# Sheet_1_2022-10-20.net
KiCad netlist of a schematic drawn in Altium Designer
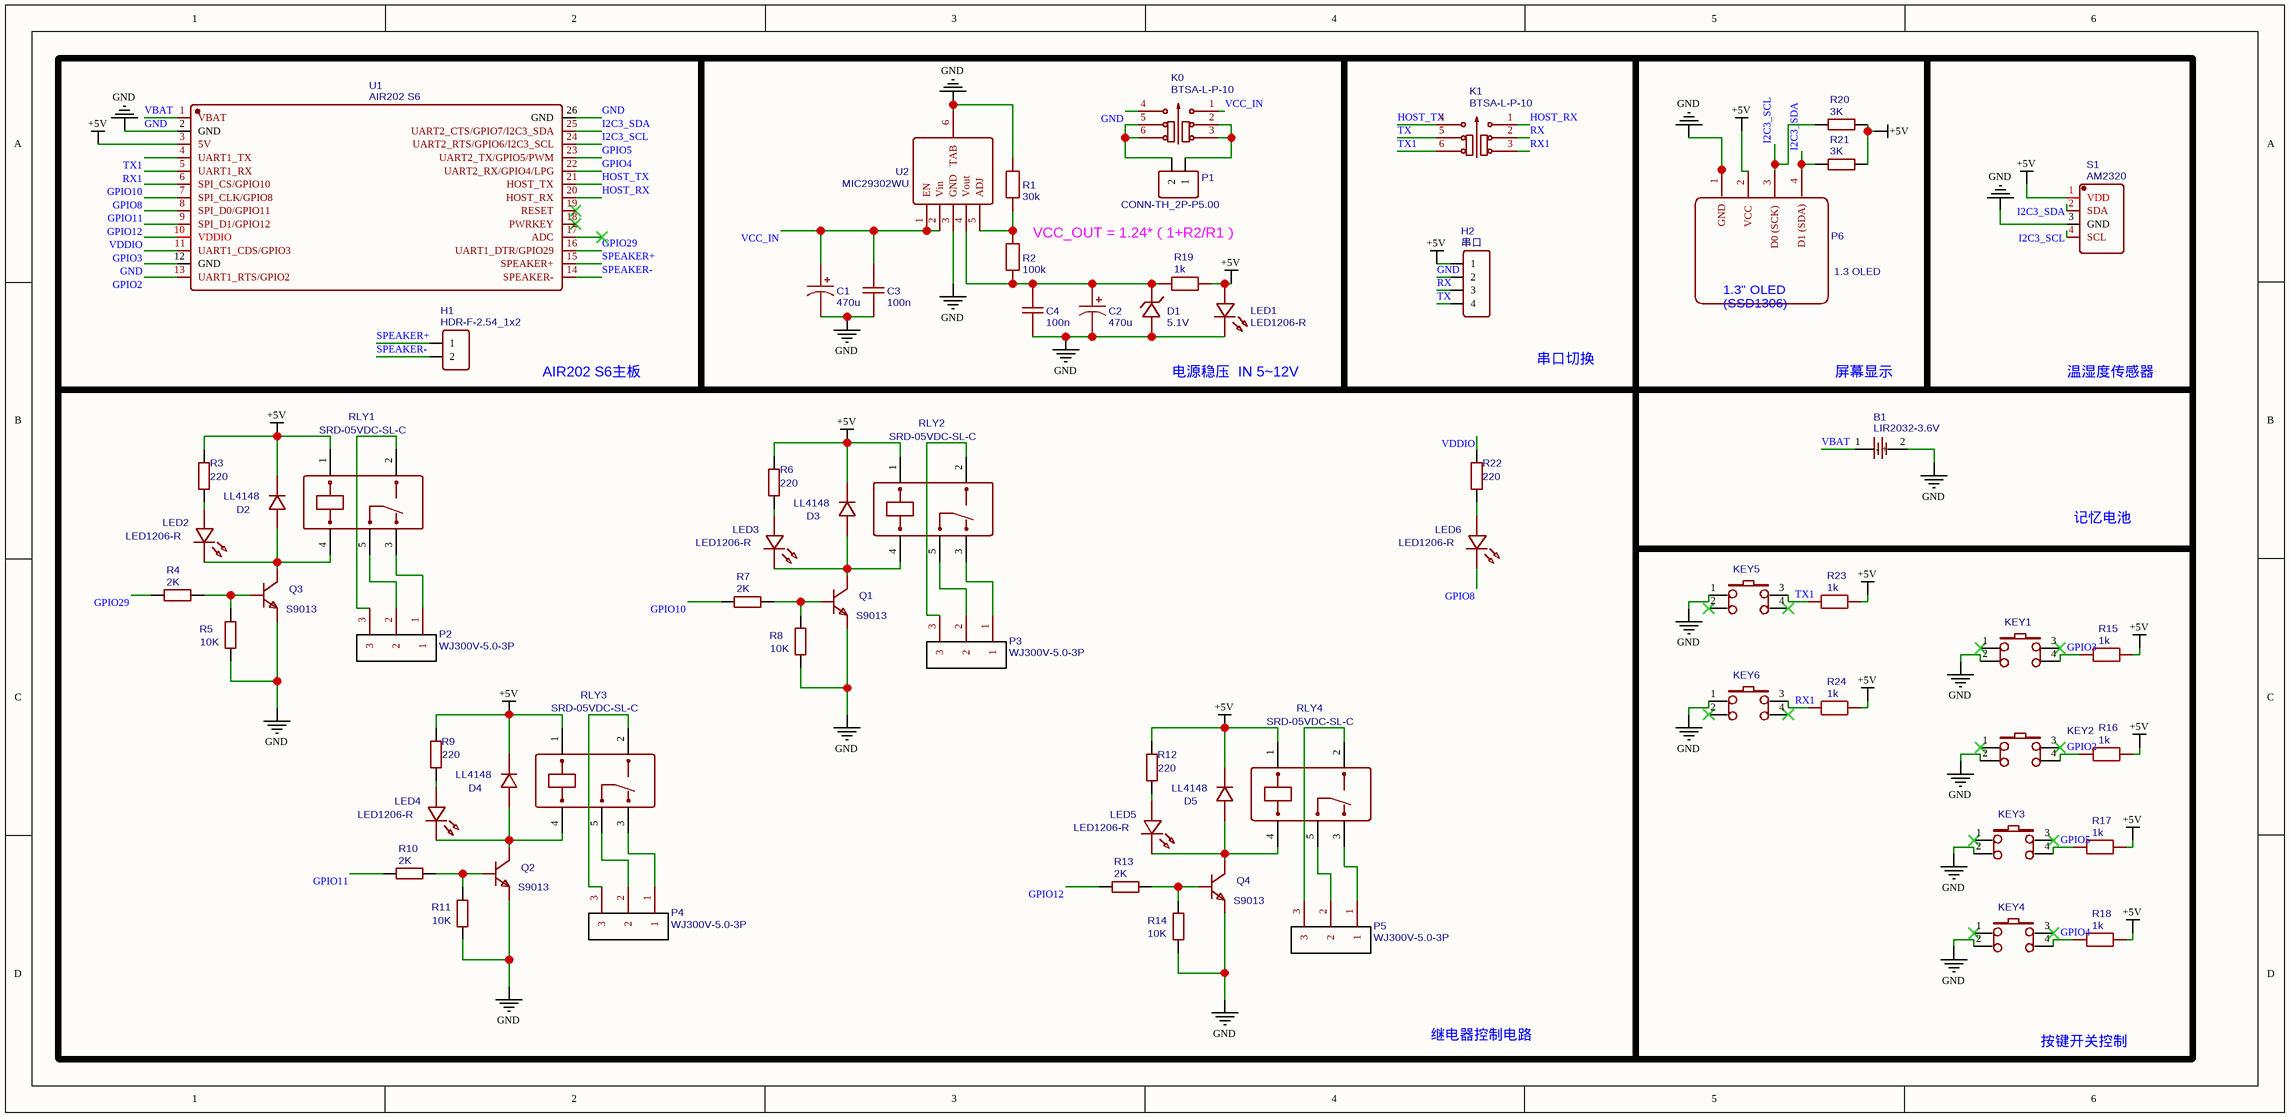
[diagram p0: Sheet_1_2022-10-20.schdoc]

(export (version "E")
  (design (tool "Eeschema 10.0.6"))
  (components
    (comp (ref "B1")
      (value "LIR2032-3.6V")
      (fields
        (field (name "BOM_MANUFACTURER PART") "CR2032-BS-6-1")
        (field (name "BOM_SUPPLIER PART") "C70377")
        (field (name "CONTRIBUTOR") "壹科团队")
      )
      (libsource (lib "altium-import") (part "root_0_LIR2032-3.6V_"))
    )
    (comp (ref "C1")
      (value "470u")
      (fields (field (name "CONTRIBUTOR") "LCEDA_Lib"))
      (libsource (lib "altium-import") (part "root_3_470u_"))
    )
    (comp (ref "C2")
      (value "470u")
      (fields (field (name "CONTRIBUTOR") "LCEDA_Lib"))
      (libsource (lib "altium-import") (part "root_3_470u_"))
    )
    (comp (ref "C3")
      (value "100n")
      (fields (field (name "CONTRIBUTOR") "LCEDA_Lib"))
      (libsource (lib "altium-import") (part "root_3_100n_"))
    )
    (comp (ref "C4")
      (value "100n")
      (fields (field (name "CONTRIBUTOR") "LCEDA_Lib"))
      (libsource (lib "altium-import") (part "root_3_100n_"))
    )
    (comp (ref "D1")
      (value "5.1V")
      (fields
        (field (name "BOM_MANUFACTURER PART") "BZD27B75P-M3-08")
        (field (name "BOM_SUPPLIER PART") "C145219")
        (field (name "CONTRIBUTOR") "LCSC")
      )
      (libsource (lib "altium-import") (part "root_3_5.1V_"))
    )
    (comp (ref "D2")
      (value "LL4148")
      (fields (field (name "BOM_SUPPLIER PART") "C84062"))
      (libsource (lib "altium-import") (part "root_3_LL4148_"))
    )
    (comp (ref "D3")
      (value "LL4148")
      (fields (field (name "BOM_SUPPLIER PART") "C84062"))
      (libsource (lib "altium-import") (part "root_3_LL4148_"))
    )
    (comp (ref "D4")
      (value "LL4148")
      (fields (field (name "BOM_SUPPLIER PART") "C84062"))
      (libsource (lib "altium-import") (part "root_3_LL4148_"))
    )
    (comp (ref "D5")
      (value "LL4148")
      (fields (field (name "BOM_SUPPLIER PART") "C84062"))
      (libsource (lib "altium-import") (part "root_3_LL4148_"))
    )
    (comp (ref "H1")
      (value "HDR-F-2.54_1x2")
      (fields (field (name "BOM_SUPPLIER PART") "C49661") (field (name "CONTRIBUTOR") "LCEDA_Lib"))
      (libsource (lib "altium-import") (part "root_0_HDR-F-2.54_1x2_"))
    )
    (comp (ref "H2")
      (value "串口")
      (fields (field (name "BOM_SUPPLIER PART") "C225501") (field (name "CONTRIBUTOR") "LCEDA_Lib"))
      (libsource (lib "altium-import") (part "root_0_串口_"))
    )
    (comp (ref "K0")
      (value "BTSA-L-P-10")
      (fields (field (name "CONTRIBUTOR") "qingsong03"))
      (libsource (lib "altium-import") (part "root_0_BTSA-L-P-10_"))
    )
    (comp (ref "K1")
      (value "BTSA-L-P-10")
      (fields (field (name "CONTRIBUTOR") "qingsong03"))
      (libsource (lib "altium-import") (part "root_0_BTSA-L-P-10_"))
    )
    (comp (ref "KEY1")
      (value "6x6x6Plastic head")
      (fields (field (name "BOM_SUPPLIER PART") "C23550"))
      (libsource (lib "altium-import") (part "root_0_6x6x6Plastic head_"))
    )
    (comp (ref "KEY2")
      (value "6x6x6Plastic head")
      (fields (field (name "BOM_SUPPLIER PART") "C23550"))
      (libsource (lib "altium-import") (part "root_0_6x6x6Plastic head_"))
    )
    (comp (ref "KEY3")
      (value "6x6x6Plastic head")
      (fields (field (name "BOM_SUPPLIER PART") "C23550"))
      (libsource (lib "altium-import") (part "root_0_6x6x6Plastic head_"))
    )
    (comp (ref "KEY4")
      (value "6x6x6Plastic head")
      (fields (field (name "BOM_SUPPLIER PART") "C23550"))
      (libsource (lib "altium-import") (part "root_0_6x6x6Plastic head_"))
    )
    (comp (ref "KEY5")
      (value "6x6x6Plastic head")
      (fields (field (name "BOM_SUPPLIER PART") "C23550"))
      (libsource (lib "altium-import") (part "root_0_6x6x6Plastic head_"))
    )
    (comp (ref "KEY6")
      (value "6x6x6Plastic head")
      (fields (field (name "BOM_SUPPLIER PART") "C23550"))
      (libsource (lib "altium-import") (part "root_0_6x6x6Plastic head_"))
    )
    (comp (ref "LED1")
      (value "LED1206-R")
      (fields
        (field (name "BOM_MANUFACTURER PART") "19-217/R6C-AL1M2VY/3T")
        (field (name "BOM_SUPPLIER PART") "C72044")
        (field (name "CONTRIBUTOR") "LCEDA_01")
      )
      (libsource (lib "altium-import") (part "root_3_LED1206-R_"))
    )
    (comp (ref "LED2")
      (value "LED1206-R")
      (fields
        (field (name "BOM_MANUFACTURER PART") "19-217/R6C-AL1M2VY/3T")
        (field (name "BOM_SUPPLIER PART") "C72044")
        (field (name "CONTRIBUTOR") "LCEDA_01")
      )
      (libsource (lib "altium-import") (part "root_3_LED1206-R_"))
    )
    (comp (ref "LED3")
      (value "LED1206-R")
      (fields
        (field (name "BOM_MANUFACTURER PART") "19-217/R6C-AL1M2VY/3T")
        (field (name "BOM_SUPPLIER PART") "C72044")
        (field (name "CONTRIBUTOR") "LCEDA_01")
      )
      (libsource (lib "altium-import") (part "root_3_LED1206-R_"))
    )
    (comp (ref "LED4")
      (value "LED1206-R")
      (fields
        (field (name "BOM_MANUFACTURER PART") "19-217/R6C-AL1M2VY/3T")
        (field (name "BOM_SUPPLIER PART") "C72044")
        (field (name "CONTRIBUTOR") "LCEDA_01")
      )
      (libsource (lib "altium-import") (part "root_3_LED1206-R_"))
    )
    (comp (ref "LED5")
      (value "LED1206-R")
      (fields
        (field (name "BOM_MANUFACTURER PART") "19-217/R6C-AL1M2VY/3T")
        (field (name "BOM_SUPPLIER PART") "C72044")
        (field (name "CONTRIBUTOR") "LCEDA_01")
      )
      (libsource (lib "altium-import") (part "root_3_LED1206-R_"))
    )
    (comp (ref "LED6")
      (value "LED1206-R")
      (fields
        (field (name "BOM_MANUFACTURER PART") "19-217/R6C-AL1M2VY/3T")
        (field (name "BOM_SUPPLIER PART") "C72044")
        (field (name "CONTRIBUTOR") "LCEDA_01")
      )
      (libsource (lib "altium-import") (part "root_3_LED1206-R_"))
    )
    (comp (ref "P1")
      (value "CONN-TH_2P-P5.00")
      (fields (field (name "CONTRIBUTOR") "LCEDA_Lib"))
      (libsource (lib "altium-import") (part "root_3_CONN-TH_2P-P5.00_"))
    )
    (comp (ref "P2")
      (value "WJ300V-5.0-3P")
      (fields (field (name "BOM_SUPPLIER PART") "C8467"))
      (libsource (lib "altium-import") (part "root_2_WJ300V-5.0-3P_"))
    )
    (comp (ref "P3")
      (value "WJ300V-5.0-3P")
      (fields (field (name "BOM_SUPPLIER PART") "C8467"))
      (libsource (lib "altium-import") (part "root_2_WJ300V-5.0-3P_"))
    )
    (comp (ref "P4")
      (value "WJ300V-5.0-3P")
      (fields (field (name "BOM_SUPPLIER PART") "C8467"))
      (libsource (lib "altium-import") (part "root_2_WJ300V-5.0-3P_"))
    )
    (comp (ref "P5")
      (value "WJ300V-5.0-3P")
      (fields (field (name "BOM_SUPPLIER PART") "C8467"))
      (libsource (lib "altium-import") (part "root_2_WJ300V-5.0-3P_"))
    )
    (comp (ref "P6") (value "1.3 OLED") (libsource (lib "altium-import") (part "root_0_1.3 OLED_")))
    (comp (ref "Q1")
      (value "S9013")
      (fields (field (name "BOM_SUPPLIER PART") "C2688220") (field (name "CONTRIBUTOR") "LCSC"))
      (libsource (lib "altium-import") (part "root_0_S9013_"))
    )
    (comp (ref "Q2")
      (value "S9013")
      (fields (field (name "BOM_SUPPLIER PART") "C2688220") (field (name "CONTRIBUTOR") "LCSC"))
      (libsource (lib "altium-import") (part "root_0_S9013_"))
    )
    (comp (ref "Q3")
      (value "S9013")
      (fields (field (name "BOM_SUPPLIER PART") "C2688220") (field (name "CONTRIBUTOR") "LCSC"))
      (libsource (lib "altium-import") (part "root_0_S9013_"))
    )
    (comp (ref "Q4")
      (value "S9013")
      (fields (field (name "BOM_SUPPLIER PART") "C2688220") (field (name "CONTRIBUTOR") "LCSC"))
      (libsource (lib "altium-import") (part "root_0_S9013_"))
    )
    (comp (ref "R1")
      (value "30k")
      (fields (field (name "CONTRIBUTOR") "LCEDA_Lib"))
      (libsource (lib "altium-import") (part "root_3_30k_"))
    )
    (comp (ref "R2")
      (value "100k")
      (fields (field (name "CONTRIBUTOR") "LCEDA_Lib"))
      (libsource (lib "altium-import") (part "root_3_100k_"))
    )
    (comp (ref "R3")
      (value "220")
      (fields
        (field (name "BOM_MANUFACTURER PART") "RTT06000JTP")
        (field (name "BOM_SUPPLIER PART") "C104592")
      )
      (libsource (lib "altium-import") (part "root_1_220_"))
    )
    (comp (ref "R4")
      (value "2K")
      (fields
        (field (name "BOM_MANUFACTURER PART") "RTT06000JTP")
        (field (name "BOM_SUPPLIER PART") "C104592")
      )
      (libsource (lib "altium-import") (part "root_0_2K_"))
    )
    (comp (ref "R5")
      (value "10K")
      (fields
        (field (name "BOM_MANUFACTURER PART") "RTT06000JTP")
        (field (name "BOM_SUPPLIER PART") "C104592")
      )
      (libsource (lib "altium-import") (part "root_3_10K_"))
    )
    (comp (ref "R6")
      (value "220")
      (fields
        (field (name "BOM_MANUFACTURER PART") "RTT06000JTP")
        (field (name "BOM_SUPPLIER PART") "C104592")
      )
      (libsource (lib "altium-import") (part "root_1_220_"))
    )
    (comp (ref "R7")
      (value "2K")
      (fields
        (field (name "BOM_MANUFACTURER PART") "RTT06000JTP")
        (field (name "BOM_SUPPLIER PART") "C104592")
      )
      (libsource (lib "altium-import") (part "root_0_2K_"))
    )
    (comp (ref "R8")
      (value "10K")
      (fields
        (field (name "BOM_MANUFACTURER PART") "RTT06000JTP")
        (field (name "BOM_SUPPLIER PART") "C104592")
      )
      (libsource (lib "altium-import") (part "root_3_10K_"))
    )
    (comp (ref "R9")
      (value "220")
      (fields
        (field (name "BOM_MANUFACTURER PART") "RTT06000JTP")
        (field (name "BOM_SUPPLIER PART") "C104592")
      )
      (libsource (lib "altium-import") (part "root_1_220_"))
    )
    (comp (ref "R10")
      (value "2K")
      (fields
        (field (name "BOM_MANUFACTURER PART") "RTT06000JTP")
        (field (name "BOM_SUPPLIER PART") "C104592")
      )
      (libsource (lib "altium-import") (part "root_0_2K_"))
    )
    (comp (ref "R11")
      (value "10K")
      (fields
        (field (name "BOM_MANUFACTURER PART") "RTT06000JTP")
        (field (name "BOM_SUPPLIER PART") "C104592")
      )
      (libsource (lib "altium-import") (part "root_3_10K_"))
    )
    (comp (ref "R12")
      (value "220")
      (fields
        (field (name "BOM_MANUFACTURER PART") "RTT06000JTP")
        (field (name "BOM_SUPPLIER PART") "C104592")
      )
      (libsource (lib "altium-import") (part "root_1_220_"))
    )
    (comp (ref "R13")
      (value "2K")
      (fields
        (field (name "BOM_MANUFACTURER PART") "RTT06000JTP")
        (field (name "BOM_SUPPLIER PART") "C104592")
      )
      (libsource (lib "altium-import") (part "root_0_2K_"))
    )
    (comp (ref "R14")
      (value "10K")
      (fields
        (field (name "BOM_MANUFACTURER PART") "RTT06000JTP")
        (field (name "BOM_SUPPLIER PART") "C104592")
      )
      (libsource (lib "altium-import") (part "root_3_10K_"))
    )
    (comp (ref "R15")
      (value "1k")
      (fields (field (name "CONTRIBUTOR") "LCEDA_Lib"))
      (libsource (lib "altium-import") (part "root_0_1k_"))
    )
    (comp (ref "R16")
      (value "1k")
      (fields (field (name "CONTRIBUTOR") "LCEDA_Lib"))
      (libsource (lib "altium-import") (part "root_0_1k_"))
    )
    (comp (ref "R17")
      (value "1k")
      (fields (field (name "CONTRIBUTOR") "LCEDA_Lib"))
      (libsource (lib "altium-import") (part "root_0_1k_"))
    )
    (comp (ref "R18")
      (value "1k")
      (fields (field (name "CONTRIBUTOR") "LCEDA_Lib"))
      (libsource (lib "altium-import") (part "root_0_1k_"))
    )
    (comp (ref "R19")
      (value "1k")
      (fields (field (name "CONTRIBUTOR") "LCEDA_Lib"))
      (libsource (lib "altium-import") (part "root_0_1k_"))
    )
    (comp (ref "R20")
      (value "3K")
      (fields
        (field (name "BOM_MANUFACTURER PART") "RTT06000JTP")
        (field (name "BOM_SUPPLIER PART") "C104592")
      )
      (libsource (lib "altium-import") (part "root_2_3K_"))
    )
    (comp (ref "R21")
      (value "3K")
      (fields
        (field (name "BOM_MANUFACTURER PART") "RTT06000JTP")
        (field (name "BOM_SUPPLIER PART") "C104592")
      )
      (libsource (lib "altium-import") (part "root_2_3K_"))
    )
    (comp (ref "R22")
      (value "220")
      (fields
        (field (name "BOM_MANUFACTURER PART") "RTT06000JTP")
        (field (name "BOM_SUPPLIER PART") "C104592")
      )
      (libsource (lib "altium-import") (part "root_1_220_"))
    )
    (comp (ref "R23")
      (value "1k")
      (fields (field (name "CONTRIBUTOR") "LCEDA_Lib"))
      (libsource (lib "altium-import") (part "root_0_1k_"))
    )
    (comp (ref "R24")
      (value "1k")
      (fields (field (name "CONTRIBUTOR") "LCEDA_Lib"))
      (libsource (lib "altium-import") (part "root_0_1k_"))
    )
    (comp (ref "RLY1")
      (value "SRD-05VDC-SL-C")
      (fields (field (name "BOM_SUPPLIER PART") "C35449"))
      (libsource (lib "altium-import") (part "root_3_SRD-05VDC-SL-C_"))
    )
    (comp (ref "RLY2")
      (value "SRD-05VDC-SL-C")
      (fields (field (name "BOM_SUPPLIER PART") "C35449"))
      (libsource (lib "altium-import") (part "root_3_SRD-05VDC-SL-C_"))
    )
    (comp (ref "RLY3")
      (value "SRD-05VDC-SL-C")
      (fields (field (name "BOM_SUPPLIER PART") "C35449"))
      (libsource (lib "altium-import") (part "root_3_SRD-05VDC-SL-C_"))
    )
    (comp (ref "RLY4")
      (value "SRD-05VDC-SL-C")
      (fields (field (name "BOM_SUPPLIER PART") "C35449"))
      (libsource (lib "altium-import") (part "root_3_SRD-05VDC-SL-C_"))
    )
    (comp (ref "S1")
      (value "AM2320")
      (fields (field (name "BOM_SUPPLIER PART") "C87932"))
      (libsource (lib "altium-import") (part "root_0_AM2320_"))
    )
    (comp (ref "U1")
      (value "AIR202 S6")
      (fields (field (name "CONTRIBUTOR") "liangen"))
      (libsource (lib "altium-import") (part "root_0_AIR202 S6_"))
    )
    (comp (ref "U2")
      (value "MIC29302WU")
      (fields (field (name "BOM_SUPPLIER PART") "C11149"))
      (libsource (lib "altium-import") (part "root_3_MIC29302WU_"))
    )
  )
  (nets
    (net (code "1") (name "+5V") (class "Default")
      (node (ref "D2") (pin "1") (pinfunction "C_1") (pintype "passive"))
      (node (ref "D3") (pin "1") (pinfunction "C_1") (pintype "passive"))
      (node (ref "D4") (pin "1") (pinfunction "C_1") (pintype "passive"))
      (node (ref "D5") (pin "1") (pinfunction "C_1") (pintype "passive"))
      (node (ref "H2") (pin "1") (pinfunction "1_1") (pintype "passive"))
      (node (ref "LED1") (pin "1") (pinfunction "1_1") (pintype "passive"))
      (node (ref "P6") (pin "2") (pinfunction "VCC_2") (pintype "passive"))
      (node (ref "R12") (pin "2") (pinfunction "2_2") (pintype "passive"))
      (node (ref "R15") (pin "2") (pinfunction "2_2") (pintype "passive"))
      (node (ref "R16") (pin "2") (pinfunction "2_2") (pintype "passive"))
      (node (ref "R17") (pin "2") (pinfunction "2_2") (pintype "passive"))
      (node (ref "R18") (pin "2") (pinfunction "2_2") (pintype "passive"))
      (node (ref "R19") (pin "2") (pinfunction "2_2") (pintype "passive"))
      (node (ref "R20") (pin "1") (pinfunction "1_1") (pintype "passive"))
      (node (ref "R21") (pin "1") (pinfunction "1_1") (pintype "passive"))
      (node (ref "R23") (pin "2") (pinfunction "2_2") (pintype "passive"))
      (node (ref "R24") (pin "2") (pinfunction "2_2") (pintype "passive"))
      (node (ref "R3") (pin "2") (pinfunction "2_2") (pintype "passive"))
      (node (ref "R6") (pin "2") (pinfunction "2_2") (pintype "passive"))
      (node (ref "R9") (pin "2") (pinfunction "2_2") (pintype "passive"))
      (node (ref "RLY1") (pin "1") (pinfunction "1_1") (pintype "passive"))
      (node (ref "RLY2") (pin "1") (pinfunction "1_1") (pintype "passive"))
      (node (ref "RLY3") (pin "1") (pinfunction "1_1") (pintype "passive"))
      (node (ref "RLY4") (pin "1") (pinfunction "1_1") (pintype "passive"))
      (node (ref "S1") (pin "1") (pinfunction "VDD_1") (pintype "passive"))
      (node (ref "U1") (pin "3") (pinfunction "5V_3") (pintype "passive"))
    )
    (net (code "2") (name "/GPIO2") (class "Default")
      (node (ref "KEY2") (pin "4") (pinfunction "4_4") (pintype "passive"))
      (node (ref "R16") (pin "1") (pinfunction "1_1") (pintype "passive"))
      (node (ref "U1") (pin "13") (pinfunction "UART1_RTS/GPIO2_13") (pintype "passive"))
    )
    (net (code "3") (name "/GPIO3") (class "Default")
      (node (ref "KEY1") (pin "4") (pinfunction "4_4") (pintype "passive"))
      (node (ref "R15") (pin "1") (pinfunction "1_1") (pintype "passive"))
      (node (ref "U1") (pin "11") (pinfunction "UART1_CDS/GPIO3_11") (pintype "passive"))
    )
    (net (code "4") (name "/GPIO4") (class "Default")
      (node (ref "KEY4") (pin "4") (pinfunction "4_4") (pintype "passive"))
      (node (ref "R18") (pin "1") (pinfunction "1_1") (pintype "passive"))
      (node (ref "U1") (pin "22") (pinfunction "UART2_RX/GPIO4/LPG_22") (pintype "passive"))
    )
    (net (code "5") (name "/GPIO5") (class "Default")
      (node (ref "KEY3") (pin "4") (pinfunction "4_4") (pintype "passive"))
      (node (ref "R17") (pin "1") (pinfunction "1_1") (pintype "passive"))
      (node (ref "U1") (pin "23") (pinfunction "UART2_TX/GPIO5/PWM_23") (pintype "passive"))
    )
    (net (code "6") (name "/GPIO8") (class "Default")
      (node (ref "LED6") (pin "2") (pinfunction "2_2") (pintype "passive"))
      (node (ref "U1") (pin "7") (pinfunction "SPI_CLK/GPIO8_7") (pintype "passive"))
    )
    (net (code "7") (name "/GPIO10") (class "Default")
      (node (ref "R7") (pin "1") (pinfunction "1_1") (pintype "passive"))
      (node (ref "U1") (pin "6") (pinfunction "SPI_CS/GPIO10_6") (pintype "passive"))
    )
    (net (code "8") (name "/GPIO11") (class "Default")
      (node (ref "R10") (pin "1") (pinfunction "1_1") (pintype "passive"))
      (node (ref "U1") (pin "8") (pinfunction "SPI_D0/GPIO11_8") (pintype "passive"))
    )
    (net (code "9") (name "/GPIO12") (class "Default")
      (node (ref "R13") (pin "1") (pinfunction "1_1") (pintype "passive"))
      (node (ref "U1") (pin "9") (pinfunction "SPI_D1/GPIO12_9") (pintype "passive"))
    )
    (net (code "10") (name "/GPIO29") (class "Default")
      (node (ref "R4") (pin "1") (pinfunction "1_1") (pintype "passive"))
      (node (ref "U1") (pin "16") (pinfunction "UART1_DTR/GPIO29_16") (pintype "passive"))
    )
    (net (code "11") (name "/HOST_RX") (class "Default")
      (node (ref "K1") (pin "1") (pinfunction "1_1") (pintype "passive"))
      (node (ref "U1") (pin "20") (pinfunction "HOST_RX_20") (pintype "passive"))
    )
    (net (code "12") (name "/HOST_TX") (class "Default")
      (node (ref "K1") (pin "4") (pinfunction "4_4") (pintype "passive"))
      (node (ref "U1") (pin "21") (pinfunction "HOST_TX_21") (pintype "passive"))
    )
    (net (code "13") (name "/I2C3_SCL") (class "Default")
      (node (ref "P6") (pin "3") (pinfunction "D0_(SCK)_3") (pintype "passive"))
      (node (ref "R20") (pin "2") (pinfunction "2_2") (pintype "passive"))
      (node (ref "S1") (pin "4") (pinfunction "SCL_4") (pintype "passive"))
      (node (ref "U1") (pin "24") (pinfunction "UART2_RTS/GPIO6/I2C3_SCL_24") (pintype "passive"))
    )
    (net (code "14") (name "/I2C3_SDA") (class "Default")
      (node (ref "P6") (pin "4") (pinfunction "D1_(SDA)_4") (pintype "passive"))
      (node (ref "R21") (pin "2") (pinfunction "2_2") (pintype "passive"))
      (node (ref "S1") (pin "2") (pinfunction "SDA_2") (pintype "passive"))
      (node (ref "U1") (pin "25") (pinfunction "UART2_CTS/GPIO7/I2C3_SDA_25") (pintype "passive"))
    )
    (net (code "15") (name "/RX") (class "Default")
      (node (ref "H2") (pin "3") (pinfunction "3_3") (pintype "passive"))
      (node (ref "K1") (pin "2") (pinfunction "2_2") (pintype "passive"))
    )
    (net (code "16") (name "/RX1") (class "Default")
      (node (ref "K1") (pin "3") (pinfunction "3_3") (pintype "passive"))
      (node (ref "KEY6") (pin "3") (pinfunction "3_3") (pintype "passive"))
      (node (ref "R24") (pin "1") (pinfunction "1_1") (pintype "passive"))
      (node (ref "U1") (pin "5") (pinfunction "UART1_RX_5") (pintype "passive"))
    )
    (net (code "17") (name "/SPEAKER+") (class "Default")
      (node (ref "H1") (pin "1") (pinfunction "1_1") (pintype "passive"))
      (node (ref "U1") (pin "15") (pinfunction "SPEAKER+_15") (pintype "passive"))
    )
    (net (code "18") (name "/SPEAKER-") (class "Default")
      (node (ref "H1") (pin "2") (pinfunction "2_2") (pintype "passive"))
      (node (ref "U1") (pin "14") (pinfunction "SPEAKER-_14") (pintype "passive"))
    )
    (net (code "19") (name "/TX") (class "Default")
      (node (ref "H2") (pin "4") (pinfunction "4_4") (pintype "passive"))
      (node (ref "K1") (pin "5") (pinfunction "5_5") (pintype "passive"))
    )
    (net (code "20") (name "/TX1") (class "Default")
      (node (ref "K1") (pin "6") (pinfunction "6_6") (pintype "passive"))
      (node (ref "KEY5") (pin "3") (pinfunction "3_3") (pintype "passive"))
      (node (ref "R23") (pin "1") (pinfunction "1_1") (pintype "passive"))
      (node (ref "U1") (pin "4") (pinfunction "UART1_TX_4") (pintype "passive"))
    )
    (net (code "21") (name "/VBAT") (class "Default")
      (node (ref "B1") (pin "1") (pinfunction "+_1") (pintype "passive"))
      (node (ref "U1") (pin "1") (pinfunction "VBAT_1") (pintype "passive"))
    )
    (net (code "22") (name "/VCC_IN") (class "Default")
      (node (ref "C1") (pin "1") (pinfunction "1_1") (pintype "passive"))
      (node (ref "C3") (pin "1") (pinfunction "1_1") (pintype "passive"))
      (node (ref "K0") (pin "1") (pinfunction "1_1") (pintype "passive"))
      (node (ref "U2") (pin "1") (pinfunction "EN_1") (pintype "passive"))
      (node (ref "U2") (pin "2") (pinfunction "Vin_2") (pintype "passive"))
    )
    (net (code "23") (name "/VDDIO") (class "Default")
      (node (ref "R22") (pin "2") (pinfunction "2_2") (pintype "passive"))
      (node (ref "U1") (pin "10") (pinfunction "VDDIO_10") (pintype "passive"))
    )
    (net (code "24") (name "GND") (class "Default")
      (node (ref "B1") (pin "2") (pinfunction "-_2") (pintype "passive"))
      (node (ref "C1") (pin "2") (pinfunction "2_2") (pintype "passive"))
      (node (ref "C2") (pin "2") (pinfunction "2_2") (pintype "passive"))
      (node (ref "C3") (pin "2") (pinfunction "2_2") (pintype "passive"))
      (node (ref "C4") (pin "2") (pinfunction "2_2") (pintype "passive"))
      (node (ref "D1") (pin "2") (pinfunction "A_2") (pintype "passive"))
      (node (ref "H2") (pin "2") (pinfunction "2_2") (pintype "passive"))
      (node (ref "K0") (pin "4") (pinfunction "4_4") (pintype "passive"))
      (node (ref "KEY1") (pin "2") (pinfunction "2_2") (pintype "passive"))
      (node (ref "KEY2") (pin "2") (pinfunction "2_2") (pintype "passive"))
      (node (ref "KEY3") (pin "2") (pinfunction "2_2") (pintype "passive"))
      (node (ref "KEY4") (pin "2") (pinfunction "2_2") (pintype "passive"))
      (node (ref "KEY5") (pin "1") (pinfunction "1_1") (pintype "passive"))
      (node (ref "KEY6") (pin "1") (pinfunction "1_1") (pintype "passive"))
      (node (ref "LED1") (pin "2") (pinfunction "2_2") (pintype "passive"))
      (node (ref "P6") (pin "1") (pinfunction "GND_1") (pintype "passive"))
      (node (ref "Q1") (pin "2") (pinfunction "E_2") (pintype "passive"))
      (node (ref "Q2") (pin "2") (pinfunction "E_2") (pintype "passive"))
      (node (ref "Q3") (pin "2") (pinfunction "E_2") (pintype "passive"))
      (node (ref "Q4") (pin "2") (pinfunction "E_2") (pintype "passive"))
      (node (ref "R1") (pin "1") (pinfunction "1_1") (pintype "passive"))
      (node (ref "R11") (pin "2") (pinfunction "2_2") (pintype "passive"))
      (node (ref "R14") (pin "2") (pinfunction "2_2") (pintype "passive"))
      (node (ref "R5") (pin "2") (pinfunction "2_2") (pintype "passive"))
      (node (ref "R8") (pin "2") (pinfunction "2_2") (pintype "passive"))
      (node (ref "S1") (pin "3") (pinfunction "GND_3") (pintype "passive"))
      (node (ref "U1") (pin "12") (pinfunction "GND_12") (pintype "passive"))
      (node (ref "U1") (pin "2") (pinfunction "GND_2") (pintype "passive"))
      (node (ref "U1") (pin "26") (pinfunction "GND_26") (pintype "passive"))
      (node (ref "U2") (pin "3") (pinfunction "GND_3") (pintype "passive"))
      (node (ref "U2") (pin "6") (pinfunction "TAB_6") (pintype "passive"))
    )
    (net (code "25") (name "Net-(D1-K)") (class "Default")
      (node (ref "C2") (pin "1") (pinfunction "1_1") (pintype "passive"))
      (node (ref "C4") (pin "1") (pinfunction "1_1") (pintype "passive"))
      (node (ref "D1") (pin "1") (pinfunction "K_1") (pintype "passive"))
      (node (ref "R19") (pin "1") (pinfunction "1_1") (pintype "passive"))
      (node (ref "R2") (pin "2") (pinfunction "2_2") (pintype "passive"))
      (node (ref "U2") (pin "4") (pinfunction "Vout_4") (pintype "passive"))
    )
    (net (code "26") (name "Net-(D2-A)") (class "Default")
      (node (ref "D2") (pin "2") (pinfunction "A_2") (pintype "passive"))
      (node (ref "LED2") (pin "2") (pinfunction "2_2") (pintype "passive"))
      (node (ref "Q3") (pin "3") (pinfunction "C_3") (pintype "passive"))
      (node (ref "RLY1") (pin "4") (pinfunction "4_4") (pintype "passive"))
    )
    (net (code "27") (name "Net-(D3-A)") (class "Default")
      (node (ref "D3") (pin "2") (pinfunction "A_2") (pintype "passive"))
      (node (ref "LED3") (pin "2") (pinfunction "2_2") (pintype "passive"))
      (node (ref "Q1") (pin "3") (pinfunction "C_3") (pintype "passive"))
      (node (ref "RLY2") (pin "4") (pinfunction "4_4") (pintype "passive"))
    )
    (net (code "28") (name "Net-(D4-A)") (class "Default")
      (node (ref "D4") (pin "2") (pinfunction "A_2") (pintype "passive"))
      (node (ref "LED4") (pin "2") (pinfunction "2_2") (pintype "passive"))
      (node (ref "Q2") (pin "3") (pinfunction "C_3") (pintype "passive"))
      (node (ref "RLY3") (pin "4") (pinfunction "4_4") (pintype "passive"))
    )
    (net (code "29") (name "Net-(D5-A)") (class "Default")
      (node (ref "D5") (pin "2") (pinfunction "A_2") (pintype "passive"))
      (node (ref "LED5") (pin "2") (pinfunction "2_2") (pintype "passive"))
      (node (ref "Q4") (pin "3") (pinfunction "C_3") (pintype "passive"))
      (node (ref "RLY4") (pin "4") (pinfunction "4_4") (pintype "passive"))
    )
    (net (code "30") (name "Net-(K0-Pad2)") (class "Default")
      (node (ref "K0") (pin "2") (pinfunction "2_2") (pintype "passive"))
      (node (ref "K0") (pin "3") (pinfunction "3_3") (pintype "passive"))
      (node (ref "P1") (pin "1") (pinfunction "1_1") (pintype "passive"))
    )
    (net (code "31") (name "Net-(K0-Pad5)") (class "Default")
      (node (ref "K0") (pin "5") (pinfunction "5_5") (pintype "passive"))
      (node (ref "K0") (pin "6") (pinfunction "6_6") (pintype "passive"))
      (node (ref "P1") (pin "2") (pinfunction "2_2") (pintype "passive"))
    )
    (net (code "32") (name "Net-(LED2-Pad1)") (class "Default")
      (node (ref "LED2") (pin "1") (pinfunction "1_1") (pintype "passive"))
      (node (ref "R3") (pin "1") (pinfunction "1_1") (pintype "passive"))
    )
    (net (code "33") (name "Net-(LED3-Pad1)") (class "Default")
      (node (ref "LED3") (pin "1") (pinfunction "1_1") (pintype "passive"))
      (node (ref "R6") (pin "1") (pinfunction "1_1") (pintype "passive"))
    )
    (net (code "34") (name "Net-(LED4-Pad1)") (class "Default")
      (node (ref "LED4") (pin "1") (pinfunction "1_1") (pintype "passive"))
      (node (ref "R9") (pin "1") (pinfunction "1_1") (pintype "passive"))
    )
    (net (code "35") (name "Net-(LED5-Pad1)") (class "Default")
      (node (ref "LED5") (pin "1") (pinfunction "1_1") (pintype "passive"))
      (node (ref "R12") (pin "1") (pinfunction "1_1") (pintype "passive"))
    )
    (net (code "36") (name "Net-(LED6-Pad1)") (class "Default")
      (node (ref "LED6") (pin "1") (pinfunction "1_1") (pintype "passive"))
      (node (ref "R22") (pin "1") (pinfunction "1_1") (pintype "passive"))
    )
    (net (code "37") (name "Net-(P2-Pad1)") (class "Default")
      (node (ref "P2") (pin "1") (pinfunction "1_1") (pintype "passive"))
      (node (ref "RLY1") (pin "3") (pinfunction "3_3") (pintype "passive"))
    )
    (net (code "38") (name "Net-(P2-Pad2)") (class "Default")
      (node (ref "P2") (pin "2") (pinfunction "2_2") (pintype "passive"))
      (node (ref "RLY1") (pin "5") (pinfunction "5_5") (pintype "passive"))
    )
    (net (code "39") (name "Net-(P2-Pad3)") (class "Default")
      (node (ref "P2") (pin "3") (pinfunction "3_3") (pintype "passive"))
      (node (ref "RLY1") (pin "2") (pinfunction "2_2") (pintype "passive"))
    )
    (net (code "40") (name "Net-(P3-Pad1)") (class "Default")
      (node (ref "P3") (pin "1") (pinfunction "1_1") (pintype "passive"))
      (node (ref "RLY2") (pin "3") (pinfunction "3_3") (pintype "passive"))
    )
    (net (code "41") (name "Net-(P3-Pad2)") (class "Default")
      (node (ref "P3") (pin "2") (pinfunction "2_2") (pintype "passive"))
      (node (ref "RLY2") (pin "5") (pinfunction "5_5") (pintype "passive"))
    )
    (net (code "42") (name "Net-(P3-Pad3)") (class "Default")
      (node (ref "P3") (pin "3") (pinfunction "3_3") (pintype "passive"))
      (node (ref "RLY2") (pin "2") (pinfunction "2_2") (pintype "passive"))
    )
    (net (code "43") (name "Net-(P4-Pad1)") (class "Default")
      (node (ref "P4") (pin "1") (pinfunction "1_1") (pintype "passive"))
      (node (ref "RLY3") (pin "3") (pinfunction "3_3") (pintype "passive"))
    )
    (net (code "44") (name "Net-(P4-Pad2)") (class "Default")
      (node (ref "P4") (pin "2") (pinfunction "2_2") (pintype "passive"))
      (node (ref "RLY3") (pin "5") (pinfunction "5_5") (pintype "passive"))
    )
    (net (code "45") (name "Net-(P4-Pad3)") (class "Default")
      (node (ref "P4") (pin "3") (pinfunction "3_3") (pintype "passive"))
      (node (ref "RLY3") (pin "2") (pinfunction "2_2") (pintype "passive"))
    )
    (net (code "46") (name "Net-(P5-Pad1)") (class "Default")
      (node (ref "P5") (pin "1") (pinfunction "1_1") (pintype "passive"))
      (node (ref "RLY4") (pin "3") (pinfunction "3_3") (pintype "passive"))
    )
    (net (code "47") (name "Net-(P5-Pad2)") (class "Default")
      (node (ref "P5") (pin "2") (pinfunction "2_2") (pintype "passive"))
      (node (ref "RLY4") (pin "5") (pinfunction "5_5") (pintype "passive"))
    )
    (net (code "48") (name "Net-(P5-Pad3)") (class "Default")
      (node (ref "P5") (pin "3") (pinfunction "3_3") (pintype "passive"))
      (node (ref "RLY4") (pin "2") (pinfunction "2_2") (pintype "passive"))
    )
    (net (code "49") (name "Net-(Q1-B)") (class "Default")
      (node (ref "Q1") (pin "1") (pinfunction "B_1") (pintype "passive"))
      (node (ref "R7") (pin "2") (pinfunction "2_2") (pintype "passive"))
      (node (ref "R8") (pin "1") (pinfunction "1_1") (pintype "passive"))
    )
    (net (code "50") (name "Net-(Q2-B)") (class "Default")
      (node (ref "Q2") (pin "1") (pinfunction "B_1") (pintype "passive"))
      (node (ref "R10") (pin "2") (pinfunction "2_2") (pintype "passive"))
      (node (ref "R11") (pin "1") (pinfunction "1_1") (pintype "passive"))
    )
    (net (code "51") (name "Net-(Q3-B)") (class "Default")
      (node (ref "Q3") (pin "1") (pinfunction "B_1") (pintype "passive"))
      (node (ref "R4") (pin "2") (pinfunction "2_2") (pintype "passive"))
      (node (ref "R5") (pin "1") (pinfunction "1_1") (pintype "passive"))
    )
    (net (code "52") (name "Net-(Q4-B)") (class "Default")
      (node (ref "Q4") (pin "1") (pinfunction "B_1") (pintype "passive"))
      (node (ref "R13") (pin "2") (pinfunction "2_2") (pintype "passive"))
      (node (ref "R14") (pin "1") (pinfunction "1_1") (pintype "passive"))
    )
    (net (code "53") (name "Net-(U2-ADJ)") (class "Default")
      (node (ref "R1") (pin "2") (pinfunction "2_2") (pintype "passive"))
      (node (ref "R2") (pin "1") (pinfunction "1_1") (pintype "passive"))
      (node (ref "U2") (pin "5") (pinfunction "ADJ_5") (pintype "passive"))
    )
    (net (code "54") (name "unconnected-(KEY1-Pad1)") (class "Default")
      (node (ref "KEY1") (pin "1") (pinfunction "1_1") (pintype "passive+no_connect"))
    )
    (net (code "55") (name "unconnected-(KEY1-Pad3)") (class "Default")
      (node (ref "KEY1") (pin "3") (pinfunction "3_3") (pintype "passive+no_connect"))
    )
    (net (code "56") (name "unconnected-(KEY2-Pad1)") (class "Default")
      (node (ref "KEY2") (pin "1") (pinfunction "1_1") (pintype "passive+no_connect"))
    )
    (net (code "57") (name "unconnected-(KEY2-Pad3)") (class "Default")
      (node (ref "KEY2") (pin "3") (pinfunction "3_3") (pintype "passive+no_connect"))
    )
    (net (code "58") (name "unconnected-(KEY3-Pad1)") (class "Default")
      (node (ref "KEY3") (pin "1") (pinfunction "1_1") (pintype "passive+no_connect"))
    )
    (net (code "59") (name "unconnected-(KEY3-Pad3)") (class "Default")
      (node (ref "KEY3") (pin "3") (pinfunction "3_3") (pintype "passive+no_connect"))
    )
    (net (code "60") (name "unconnected-(KEY4-Pad1)") (class "Default")
      (node (ref "KEY4") (pin "1") (pinfunction "1_1") (pintype "passive+no_connect"))
    )
    (net (code "61") (name "unconnected-(KEY4-Pad3)") (class "Default")
      (node (ref "KEY4") (pin "3") (pinfunction "3_3") (pintype "passive+no_connect"))
    )
    (net (code "62") (name "unconnected-(KEY5-Pad2)") (class "Default")
      (node (ref "KEY5") (pin "2") (pinfunction "2_2") (pintype "passive+no_connect"))
    )
    (net (code "63") (name "unconnected-(KEY5-Pad4)") (class "Default")
      (node (ref "KEY5") (pin "4") (pinfunction "4_4") (pintype "passive+no_connect"))
    )
    (net (code "64") (name "unconnected-(KEY6-Pad2)") (class "Default")
      (node (ref "KEY6") (pin "2") (pinfunction "2_2") (pintype "passive+no_connect"))
    )
    (net (code "65") (name "unconnected-(KEY6-Pad4)") (class "Default")
      (node (ref "KEY6") (pin "4") (pinfunction "4_4") (pintype "passive+no_connect"))
    )
    (net (code "66") (name "unconnected-(U1-ADC-Pad17)") (class "Default")
      (node (ref "U1") (pin "17") (pinfunction "ADC_17") (pintype "passive+no_connect"))
    )
    (net (code "67") (name "unconnected-(U1-PWRKEY-Pad18)") (class "Default")
      (node (ref "U1") (pin "18") (pinfunction "PWRKEY_18") (pintype "passive+no_connect"))
    )
    (net (code "68") (name "unconnected-(U1-RESET-Pad19)") (class "Default")
      (node (ref "U1") (pin "19") (pinfunction "RESET_19") (pintype "passive+no_connect"))
    )
  )
)
